# SD_Card.net
KiCad netlist of a schematic drawn in Altium Designer
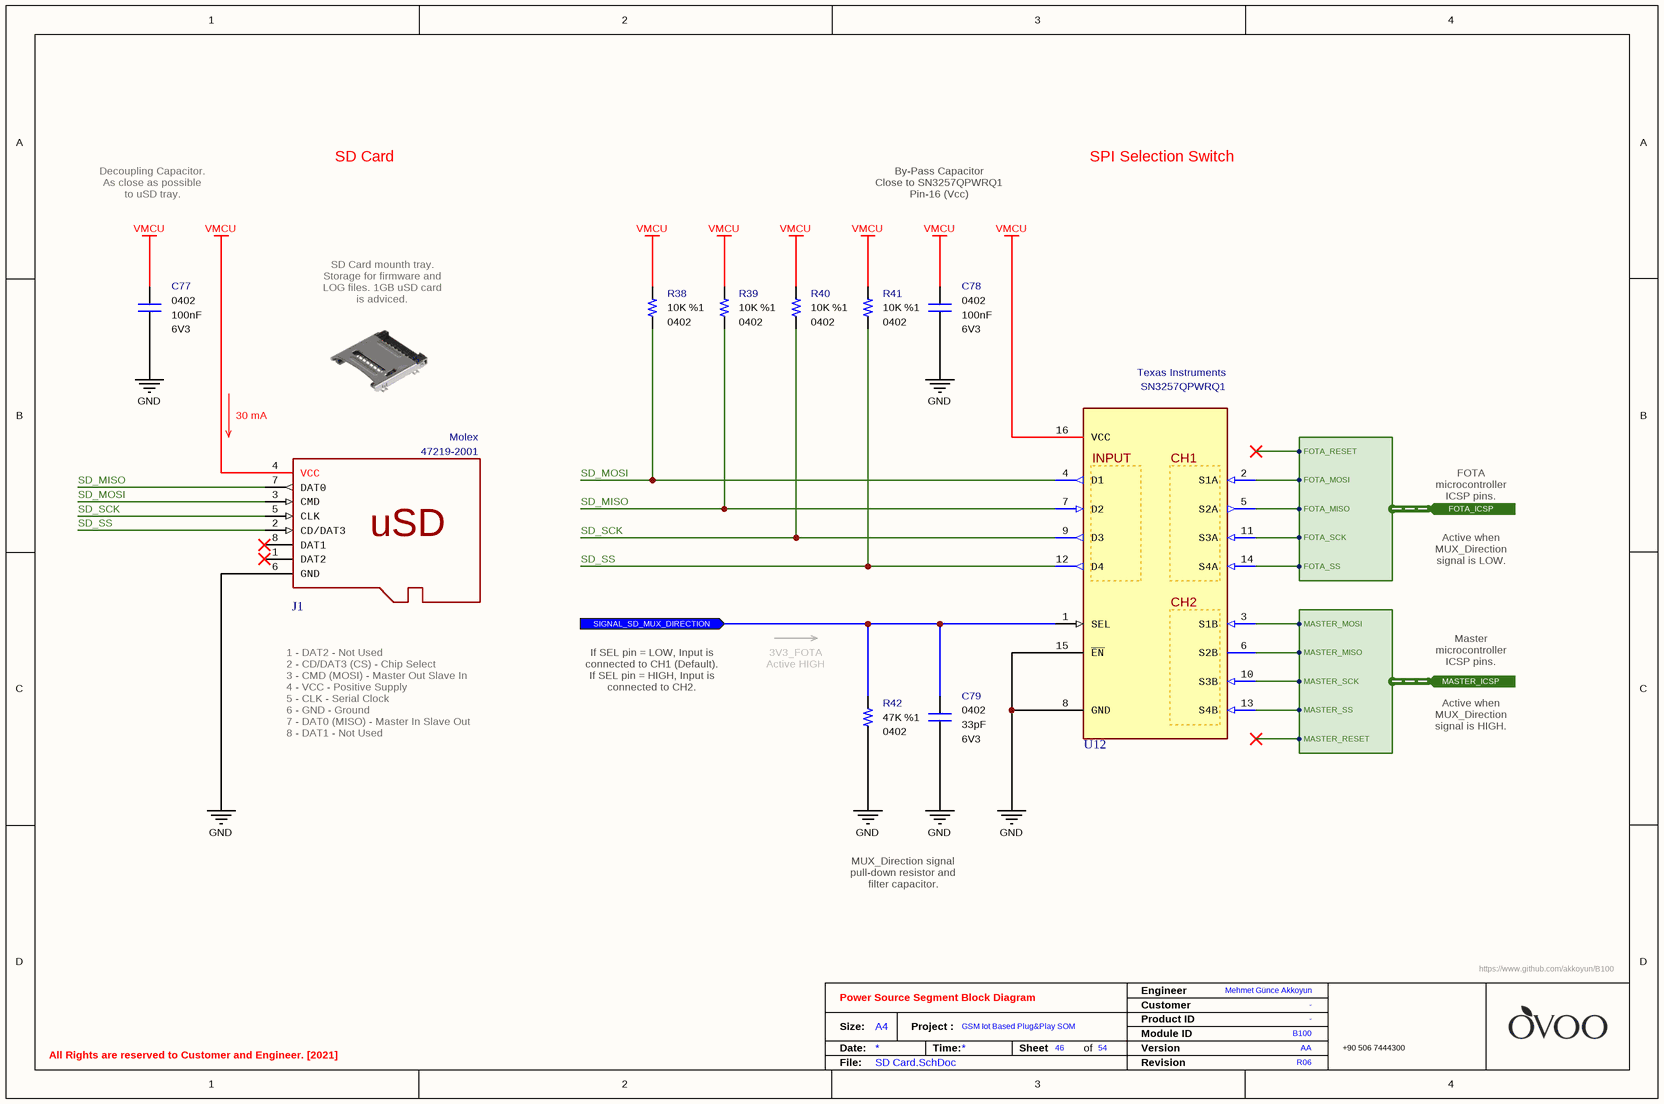
[diagram p0: SD Card.SchDoc]

(export (version "E")
  (design (tool "Eeschema 10.0.6"))
  (components
    (comp (ref "C77")
      (value "100nF")
      (footprint "CAPACITOR_0402")
      (description "Capacitor - 100nF [0402-6V3] (Ceramic)")
      (fields
        (field (name "TOLERANCE") "%10")
        (field (name "CASE") "0402")
        (field (name "VOLTAGE") "6V3")
        (field (name "MANUFACTURER PART NUMBER") "04026D104KAT4A")
      )
      (libsource (lib "Ovoo_Library") (part "Capacitor - 100nF [0402-6V3]"))
    )
    (comp (ref "C78")
      (value "100nF")
      (footprint "CAPACITOR_0402")
      (description "Capacitor - 100nF [0402-6V3] (Ceramic)")
      (fields
        (field (name "CASE") "0402")
        (field (name "TOLERANCE") "%10")
        (field (name "VOLTAGE") "6V3")
        (field (name "MANUFACTURER PART NUMBER") "04026D104KAT4A")
      )
      (libsource (lib "Ovoo_Library") (part "Capacitor - 100nF [0402-6V3]"))
    )
    (comp (ref "C79")
      (value "33pF")
      (footprint "CAPACITOR_0402")
      (description "Capacitor - 33pF [0402] (Ceramic)")
      (fields
        (field (name "TOLERANCE") "10%")
        (field (name "CASE") "0402")
        (field (name "VOLTAGE") "6V3")
        (field (name "MANUFACTURER PART NUMBER") "C0402C330J9RACAUTO")
      )
      (libsource (lib "Ovoo_Library") (part "Capacitor - 33pF [0402-6V3]"))
    )
    (comp (ref "J1")
      (value "Memory Card Connectors")
      (footprint "Connector - SD Module")
      (description "Memory Card Connectors TFR READER (HINGE TYPE)")
      (fields
        (field (name "MOUSER PART NUMBER") "538-47219-2001")
        (field (name "MANUFACTURER PART NUMBER") "47219-2001")
        (field (name "MANUFACTURER NAME") "Molex")
      )
      (libsource (lib "Ovoo_Library") (part "Connector - SD Slot"))
    )
    (comp (ref "R38")
      (value "10K")
      (footprint "RESISTOR_0402")
      (description "Thick Film Resistors - SMD 1/16 W 10 Kohms 1%")
      (fields
        (field (name "TOLERANCE") "%1")
        (field (name "CASE") "0402")
        (field (name "MANUFACTURER PART NUMBER") "CRCW040210K0FKED")
        (field (name "MOUSER PART NUMBER") "71-CRCW0402-10K-E3")
      )
      (libsource (lib "Ovoo_Library") (part "Resistor - 10K"))
    )
    (comp (ref "R39")
      (value "10K")
      (footprint "RESISTOR_0402")
      (description "Thick Film Resistors - SMD 1/16 W 10 Kohms 1%")
      (fields
        (field (name "TOLERANCE") "%1")
        (field (name "CASE") "0402")
        (field (name "MANUFACTURER PART NUMBER") "CRCW040210K0FKED")
        (field (name "MOUSER PART NUMBER") "71-CRCW0402-10K-E3")
      )
      (libsource (lib "Ovoo_Library") (part "Resistor - 10K"))
    )
    (comp (ref "R40")
      (value "10K")
      (footprint "RESISTOR_0402")
      (description "Thick Film Resistors - SMD 1/16 W 10 Kohms 1%")
      (fields
        (field (name "TOLERANCE") "%1")
        (field (name "CASE") "0402")
        (field (name "MANUFACTURER PART NUMBER") "CRCW040210K0FKED")
        (field (name "MOUSER PART NUMBER") "71-CRCW0402-10K-E3")
      )
      (libsource (lib "Ovoo_Library") (part "Resistor - 10K"))
    )
    (comp (ref "R41")
      (value "10K")
      (footprint "RESISTOR_0402")
      (description "Thick Film Resistors - SMD 1/16 W 10 Kohms 1%")
      (fields
        (field (name "TOLERANCE") "%1")
        (field (name "CASE") "0402")
        (field (name "MANUFACTURER PART NUMBER") "CRCW040210K0FKED")
        (field (name "MOUSER PART NUMBER") "71-CRCW0402-10K-E3")
      )
      (libsource (lib "Ovoo_Library") (part "Resistor - 10K"))
    )
    (comp (ref "R42")
      (value "47K")
      (footprint "RESISTOR_0402")
      (description "Thick Film Resistors - SMD 1/16 W 47 Kohms 1%")
      (fields
        (field (name "TOLERANCE") "%1")
        (field (name "CASE") "0402")
        (field (name "MANUFACTURER PART NUMBER") "CRCW040247K0FKED")
        (field (name "MOUSER PART NUMBER") "71-CRCW0402-47K-E3")
      )
      (libsource (lib "Ovoo_Library") (part "Resistor - 47K"))
    )
    (comp (ref "U12")
      (value "SPI Switch IC")
      (footprint "TSSOP-16")
      (description "Analogue Switch ICs 2:1 (SPDT), 4-channel switch with 1.8-V logic 16-TSSOP -40 to 125")
      (fields
        (field (name "MOUSER PART NUMBER") "595-SN3257QPWRQ1")
        (field (name "MANUFACTURER PART NUMBER") "SN3257QPWRQ1")
        (field (name "MANUFACTURER NAME") "Texas Instruments")
      )
      (libsource (lib "Ovoo_Library") (part "IC - SN3257QPWRQ1"))
    )
  )
  (nets
    (net (code "3") (name "/FOTA_MISO") (class "Default")
      (node (ref "U12") (pin "5") (pinfunction "S2A_5") (pintype "output"))
    )
    (net (code "4") (name "/FOTA_MOSI") (class "Default")
      (node (ref "U12") (pin "2") (pinfunction "S1A_2") (pintype "input"))
    )
    (net (code "6") (name "/FOTA_SCK") (class "Default")
      (node (ref "U12") (pin "11") (pinfunction "S3A_11") (pintype "input"))
    )
    (net (code "7") (name "/FOTA_SS") (class "Default")
      (node (ref "U12") (pin "14") (pinfunction "S4A_14") (pintype "input"))
    )
    (net (code "8") (name "/MASTER_MISO") (class "Default")
      (node (ref "U12") (pin "6") (pinfunction "S2B_6") (pintype "passive"))
    )
    (net (code "9") (name "/MASTER_MOSI") (class "Default")
      (node (ref "U12") (pin "3") (pinfunction "S1B_3") (pintype "input"))
    )
    (net (code "11") (name "/MASTER_SCK") (class "Default")
      (node (ref "U12") (pin "10") (pinfunction "S3B_10") (pintype "input"))
    )
    (net (code "12") (name "/MASTER_SS") (class "Default")
      (node (ref "U12") (pin "13") (pinfunction "S4B_13") (pintype "input"))
    )
    (net (code "13") (name "/SD_MISO") (class "Default")
      (node (ref "J1") (pin "7") (pinfunction "DAT0_7") (pintype "output"))
      (node (ref "R39") (pin "1") (pinfunction "1_1") (pintype "passive"))
      (node (ref "U12") (pin "7") (pinfunction "D2_7") (pintype "input"))
    )
    (net (code "14") (name "/SD_MOSI") (class "Default")
      (node (ref "J1") (pin "3") (pinfunction "CMD_3") (pintype "input"))
      (node (ref "R38") (pin "1") (pinfunction "1_1") (pintype "passive"))
      (node (ref "U12") (pin "4") (pinfunction "D1_4") (pintype "output"))
    )
    (net (code "15") (name "/SD_SCK") (class "Default")
      (node (ref "J1") (pin "5") (pinfunction "CLK_5") (pintype "input"))
      (node (ref "R40") (pin "1") (pinfunction "1_1") (pintype "passive"))
      (node (ref "U12") (pin "9") (pinfunction "D3_9") (pintype "output"))
    )
    (net (code "16") (name "/SD_SS") (class "Default")
      (node (ref "J1") (pin "2") (pinfunction "CD/DAT3_2") (pintype "input"))
      (node (ref "R41") (pin "1") (pinfunction "1_1") (pintype "passive"))
      (node (ref "U12") (pin "12") (pinfunction "D4_12") (pintype "output"))
    )
    (net (code "17") (name "/SIGNAL_SD_MUX_DIRECTION") (class "Default")
      (node (ref "C79") (pin "2") (pinfunction "2_2") (pintype "passive"))
      (node (ref "R42") (pin "2") (pinfunction "2_2") (pintype "passive"))
      (node (ref "U12") (pin "1") (pinfunction "SEL_1") (pintype "input"))
    )
    (net (code "20") (name "GND") (class "Default")
      (node (ref "C77") (pin "1") (pinfunction "1_1") (pintype "passive"))
      (node (ref "C78") (pin "2") (pinfunction "2_2") (pintype "passive"))
      (node (ref "C79") (pin "1") (pinfunction "1_1") (pintype "passive"))
      (node (ref "J1") (pin "6") (pinfunction "GND_6") (pintype "passive"))
      (node (ref "R42") (pin "1") (pinfunction "1_1") (pintype "passive"))
      (node (ref "U12") (pin "15") (pinfunction "~{EN}_15") (pintype "power_in"))
      (node (ref "U12") (pin "8") (pinfunction "GND_8") (pintype "power_in"))
    )
    (net (code "21") (name "VMCU") (class "Default")
      (node (ref "C77") (pin "2") (pinfunction "2_2") (pintype "passive"))
      (node (ref "C78") (pin "1") (pinfunction "1_1") (pintype "passive"))
      (node (ref "J1") (pin "4") (pinfunction "VCC_4") (pintype "passive"))
      (node (ref "R38") (pin "2") (pinfunction "2_2") (pintype "passive"))
      (node (ref "R39") (pin "2") (pinfunction "2_2") (pintype "passive"))
      (node (ref "R40") (pin "2") (pinfunction "2_2") (pintype "passive"))
      (node (ref "R41") (pin "2") (pinfunction "2_2") (pintype "passive"))
      (node (ref "U12") (pin "16") (pinfunction "VCC_16") (pintype "power_in"))
    )
    (net (code "22") (name "unconnected-(J1-DAT1-Pad8)") (class "Default")
      (node (ref "J1") (pin "8") (pinfunction "DAT1_8") (pintype "passive+no_connect"))
    )
    (net (code "23") (name "unconnected-(J1-DAT2-Pad1)") (class "Default")
      (node (ref "J1") (pin "1") (pinfunction "DAT2_1") (pintype "passive+no_connect"))
    )
  )
)
